# CMC.net
KiCad netlist of a schematic drawn in Altium Designer
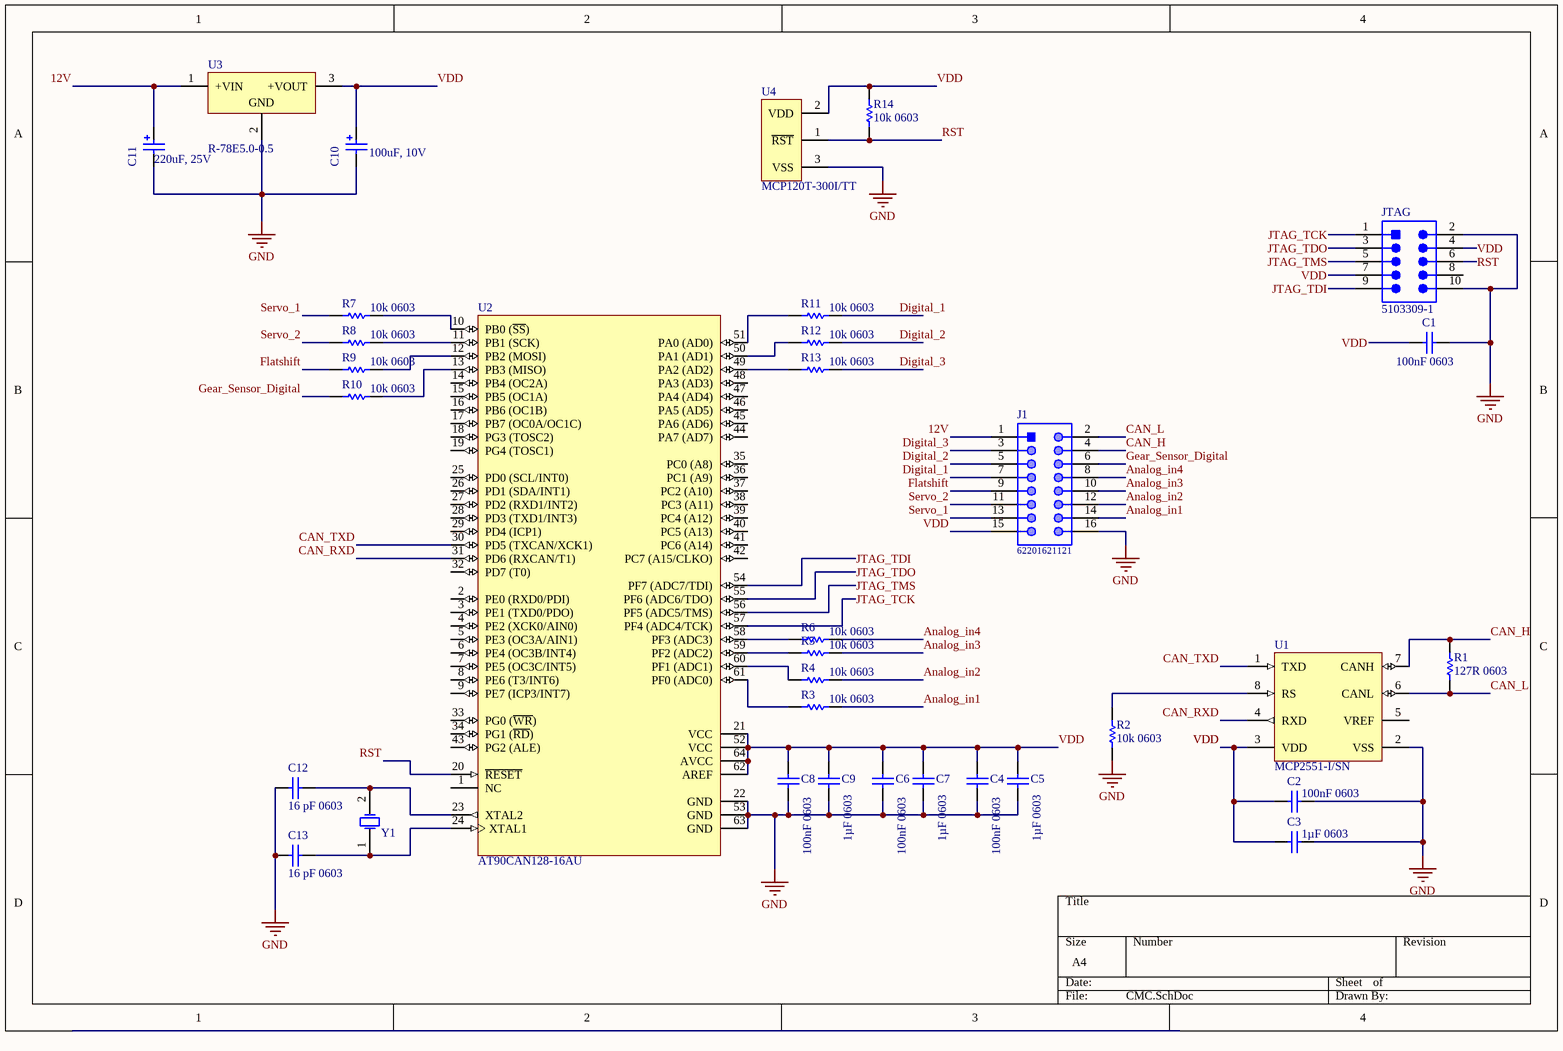
[diagram p0: CMC.SchDoc]

(export (version "E")
  (design (tool "Eeschema 10.0.6"))
  (components
    (comp (ref "C1")
      (value "100nF 0603")
      (footprint "CAPC0603(1608)100_L")
      (description "CAP 100nF 10V ±5% 0603 (1608 Metric) Thickness 1mm SMD")
      (fields (field (name "TOLERANCE") "Â±5%"))
      (libsource (lib "Altium Content Vault") (part "CAP"))
    )
    (comp (ref "C2")
      (value "100nF 0603")
      (footprint "CAPC0603(1608)100_L")
      (description "CAP 100nF 10V ±5% 0603 (1608 Metric) Thickness 1mm SMD")
      (fields (field (name "TOLERANCE") "Â±5%"))
      (libsource (lib "Altium Content Vault") (part "CAP"))
    )
    (comp (ref "C3")
      (value "1µF 0603")
      (footprint "CAPC0603(1608)100_L")
      (description "CAP 100nF 10V ±5% 0603 (1608 Metric) Thickness 1mm SMD")
      (fields (field (name "TOLERANCE") "Â±5%"))
      (libsource (lib "Altium Content Vault") (part "CAP"))
    )
    (comp (ref "C4")
      (value "100nF 0603")
      (footprint "CAPC0603(1608)100_L")
      (description "CAP 100nF 10V ±5% 0603 (1608 Metric) Thickness 1mm SMD")
      (fields (field (name "TOLERANCE") "Â±5%"))
      (libsource (lib "Altium Content Vault") (part "CAP"))
    )
    (comp (ref "C5")
      (value "1µF 0603")
      (footprint "CAPC0603(1608)100_L")
      (description "CAP 100nF 10V ±5% 0603 (1608 Metric) Thickness 1mm SMD")
      (fields (field (name "TOLERANCE") "Â±5%"))
      (libsource (lib "Altium Content Vault") (part "CAP"))
    )
    (comp (ref "C6")
      (value "100nF 0603")
      (footprint "CAPC0603(1608)100_L")
      (description "CAP 100nF 10V ±5% 0603 (1608 Metric) Thickness 1mm SMD")
      (fields (field (name "TOLERANCE") "Â±5%"))
      (libsource (lib "Altium Content Vault") (part "CAP"))
    )
    (comp (ref "C7")
      (value "1µF 0603")
      (footprint "CAPC0603(1608)100_L")
      (description "CAP 100nF 10V ±5% 0603 (1608 Metric) Thickness 1mm SMD")
      (fields (field (name "TOLERANCE") "Â±5%"))
      (libsource (lib "Altium Content Vault") (part "CAP"))
    )
    (comp (ref "C8")
      (value "100nF 0603")
      (footprint "CAPC0603(1608)100_L")
      (description "CAP 100nF 10V ±5% 0603 (1608 Metric) Thickness 1mm SMD")
      (fields (field (name "TOLERANCE") "Â±5%"))
      (libsource (lib "Altium Content Vault") (part "CAP"))
    )
    (comp (ref "C9")
      (value "1µF 0603")
      (footprint "CAPC0603(1608)100_L")
      (description "CAP 100nF 10V ±5% 0603 (1608 Metric) Thickness 1mm SMD")
      (fields (field (name "TOLERANCE") "Â±5%"))
      (libsource (lib "Altium Content Vault") (part "CAP"))
    )
    (comp (ref "C10")
      (value "100uF, 10V")
      (footprint "WCAP-ASLU_6.3x7.7")
      (description "WCAP-ASLU Aluminium Electrolytic Capacitors, D6.3mm x L7.7mm, 100uF, +/-20%, 10VDC")
      (fields (field (name "PART NUMBER") "865090245005") (field (name "PUBLISHER") "Wurth Elektronik"))
      (libsource (lib "Altium_WCAP-ASLU (rev19a)") (part "865090245005"))
    )
    (comp (ref "C11")
      (value "220uF, 25V")
      (footprint "WCAP-ATET_10x12.5")
      (description "WCAP-ATET THT Aluminum Electrolytic Capacitors, D10mm x L12.5mm, 220uF, +/-20%, 25VDC")
      (fields (field (name "PART NUMBER") "860130475006") (field (name "PUBLISHER") "Wurth Elektronik"))
      (libsource (lib "Altium_WCAP-ATET (rev19a)") (part "860130475006"))
    )
    (comp (ref "C12")
      (value "16 pF 0603")
      (footprint "CAPC0603(1608)100_L")
      (description "CAP 100nF 10V ±5% 0603 (1608 Metric) Thickness 1mm SMD")
      (fields (field (name "TOLERANCE") "Â±5%"))
      (libsource (lib "Altium Content Vault") (part "CAP"))
    )
    (comp (ref "C13")
      (value "16 pF 0603")
      (footprint "CAPC0603(1608)100_L")
      (description "CAP 100nF 10V ±5% 0603 (1608 Metric) Thickness 1mm SMD")
      (fields (field (name "TOLERANCE") "Â±5%"))
      (libsource (lib "Altium Content Vault") (part "CAP"))
    )
    (comp (ref "J1")
      (value "62201621121")
      (footprint "62201621121")
      (description "THT Vertical Pin Header WR-PHD, Pitch 1.27 mm, Dual Row, 16 pins")
      (fields (field (name "MANUFACTURER") "Wurth Elektronik") (field (name "PUBLISHER") "WurthElektronik"))
      (libsource (lib "Altium Content Vault") (part "WE-CN-2P-M-R16"))
    )
    (comp (ref "JTAG")
      (value "5103309-1")
      (footprint "TECO-5103309-1_V")
      (fields (field (name "MANUFACTURER") "TE Connectivity"))
      (libsource (lib "Altium Content Vault") (part "CN-2P-M-R10"))
    )
    (comp (ref "R1")
      (value "127R 0603")
      (footprint "RESC0603(1608)_N")
      (description "127R 0.1W 1% 0603 (1608 Metric)  SMD")
      (fields (field (name "POWER") "0.1 W") (field (name "TOLERANCE") "1 %"))
      (libsource (lib "Altium Content Vault") (part "RES"))
    )
    (comp (ref "R2")
      (value "10k 0603")
      (footprint "RESC0603(1608)_N")
      (description "127R 0.1W 1% 0603 (1608 Metric)  SMD")
      (fields (field (name "POWER") "0.1 W") (field (name "TOLERANCE") "1 %"))
      (libsource (lib "Altium Content Vault") (part "RES"))
    )
    (comp (ref "R3")
      (value "10k 0603")
      (footprint "RESC0603(1608)_N")
      (description "127R 0.1W 1% 0603 (1608 Metric)  SMD")
      (fields (field (name "POWER") "0.1 W") (field (name "TOLERANCE") "1 %"))
      (libsource (lib "Altium Content Vault") (part "RES"))
    )
    (comp (ref "R4")
      (value "10k 0603")
      (footprint "RESC0603(1608)_N")
      (description "127R 0.1W 1% 0603 (1608 Metric)  SMD")
      (fields (field (name "POWER") "0.1 W") (field (name "TOLERANCE") "1 %"))
      (libsource (lib "Altium Content Vault") (part "RES"))
    )
    (comp (ref "R5")
      (value "10k 0603")
      (footprint "RESC0603(1608)_N")
      (description "127R 0.1W 1% 0603 (1608 Metric)  SMD")
      (fields (field (name "POWER") "0.1 W") (field (name "TOLERANCE") "1 %"))
      (libsource (lib "Altium Content Vault") (part "RES"))
    )
    (comp (ref "R6")
      (value "10k 0603")
      (footprint "RESC0603(1608)_N")
      (description "127R 0.1W 1% 0603 (1608 Metric)  SMD")
      (fields (field (name "POWER") "0.1 W") (field (name "TOLERANCE") "1 %"))
      (libsource (lib "Altium Content Vault") (part "RES"))
    )
    (comp (ref "R7")
      (value "10k 0603")
      (footprint "RESC0603(1608)_N")
      (description "127R 0.1W 1% 0603 (1608 Metric)  SMD")
      (fields (field (name "POWER") "0.1 W") (field (name "TOLERANCE") "1 %"))
      (libsource (lib "Altium Content Vault") (part "RES"))
    )
    (comp (ref "R8")
      (value "10k 0603")
      (footprint "RESC0603(1608)_N")
      (description "127R 0.1W 1% 0603 (1608 Metric)  SMD")
      (fields (field (name "POWER") "0.1 W") (field (name "TOLERANCE") "1 %"))
      (libsource (lib "Altium Content Vault") (part "RES"))
    )
    (comp (ref "R9")
      (value "10k 0603")
      (footprint "RESC0603(1608)_N")
      (description "127R 0.1W 1% 0603 (1608 Metric)  SMD")
      (fields (field (name "POWER") "0.1 W") (field (name "TOLERANCE") "1 %"))
      (libsource (lib "Altium Content Vault") (part "RES"))
    )
    (comp (ref "R10")
      (value "10k 0603")
      (footprint "RESC0603(1608)_N")
      (description "127R 0.1W 1% 0603 (1608 Metric)  SMD")
      (fields (field (name "POWER") "0.1 W") (field (name "TOLERANCE") "1 %"))
      (libsource (lib "Altium Content Vault") (part "RES"))
    )
    (comp (ref "R11")
      (value "10k 0603")
      (footprint "RESC0603(1608)_N")
      (description "127R 0.1W 1% 0603 (1608 Metric)  SMD")
      (fields (field (name "POWER") "0.1 W") (field (name "TOLERANCE") "1 %"))
      (libsource (lib "Altium Content Vault") (part "RES"))
    )
    (comp (ref "R12")
      (value "10k 0603")
      (footprint "RESC0603(1608)_N")
      (description "127R 0.1W 1% 0603 (1608 Metric)  SMD")
      (fields (field (name "POWER") "0.1 W") (field (name "TOLERANCE") "1 %"))
      (libsource (lib "Altium Content Vault") (part "RES"))
    )
    (comp (ref "R13")
      (value "10k 0603")
      (footprint "RESC0603(1608)_N")
      (description "127R 0.1W 1% 0603 (1608 Metric)  SMD")
      (fields (field (name "POWER") "0.1 W") (field (name "TOLERANCE") "1 %"))
      (libsource (lib "Altium Content Vault") (part "RES"))
    )
    (comp (ref "R14")
      (value "10k 0603")
      (footprint "RESC0603(1608)_N")
      (description "127R 0.1W 1% 0603 (1608 Metric)  SMD")
      (fields (field (name "POWER") "0.1 W") (field (name "TOLERANCE") "1 %"))
      (libsource (lib "Altium Content Vault") (part "RES"))
    )
    (comp (ref "U1")
      (value "MCP2551-I/SN")
      (footprint "MCHP-SN8_V")
      (fields (field (name "MANUFACTURER") "Microchip"))
      (libsource (lib "Altium Content Vault") (part "MCHP-MCP2551-SN8"))
    )
    (comp (ref "U2")
      (value "AT90CAN128-16AU")
      (footprint "64A_M")
      (libsource (lib "Altium Content Vault") (part "MC-8B-AT90CAN32-SQ64"))
    )
    (comp (ref "U3")
      (value "R-78E5.0-0.5")
      (footprint "REPO-R-78E-0.5-3_V")
      (description "DC/DC-Converter, 5 V Single Output, 500 mA, -40 to 85 degC, 3-Pin THD, RoHS, Tube")
      (fields (field (name "MANUFACTURER") "Recom Power"))
      (libsource (lib "Altium Content Vault") (part "REPO-R-78XX-3"))
    )
    (comp (ref "U4")
      (value "MCP120T-300I/TT")
      (footprint "SOT-23-TT3_N")
      (libsource (lib "Altium Content Vault") (part "PM-SCCT-MCP120-3"))
    )
    (comp (ref "Y1")
      (value "16MHz, +/-30ppm, 16pF")
      (footprint "WE-XTAL_HC49/4HSMX")
      (description "WE-XTAL Quartz Crystal, size HC49-4HSMX, 16MHz, +/-30ppm, 16pF")
      (fields (field (name "PART NUMBER") "830003237") (field (name "PUBLISHER") "Wurth Elektronik"))
      (libsource (lib "Altium_WE-XTAL (rev19a)") (part "830003237"))
    )
  )
  (nets
    (net (code "1") (name "/12V") (class "Default")
      (node (ref "C11") (pin "2") (pinfunction "P_2") (pintype "passive"))
      (node (ref "J1") (pin "1") (pinfunction "1_1") (pintype "passive"))
      (node (ref "U3") (pin "1") (pinfunction "+VIN_1") (pintype "power_in"))
    )
    (net (code "2") (name "/Analog_in1") (class "Default")
      (node (ref "J1") (pin "14") (pinfunction "14_14") (pintype "passive"))
      (node (ref "R3") (pin "1") (pinfunction "1_1") (pintype "passive"))
    )
    (net (code "3") (name "/Analog_in2") (class "Default")
      (node (ref "J1") (pin "12") (pinfunction "12_12") (pintype "passive"))
      (node (ref "R4") (pin "1") (pinfunction "1_1") (pintype "passive"))
    )
    (net (code "4") (name "/Analog_in3") (class "Default")
      (node (ref "J1") (pin "10") (pinfunction "10_10") (pintype "passive"))
      (node (ref "R5") (pin "1") (pinfunction "1_1") (pintype "passive"))
    )
    (net (code "5") (name "/Analog_in4") (class "Default")
      (node (ref "J1") (pin "8") (pinfunction "8_8") (pintype "passive"))
      (node (ref "R6") (pin "1") (pinfunction "1_1") (pintype "passive"))
    )
    (net (code "6") (name "/CAN_H") (class "Default")
      (node (ref "J1") (pin "4") (pinfunction "4_4") (pintype "passive"))
      (node (ref "R1") (pin "2") (pinfunction "2_2") (pintype "passive"))
      (node (ref "U1") (pin "7") (pinfunction "CANH_7") (pintype "bidirectional"))
    )
    (net (code "7") (name "/CAN_L") (class "Default")
      (node (ref "J1") (pin "2") (pinfunction "2_2") (pintype "passive"))
      (node (ref "R1") (pin "1") (pinfunction "1_1") (pintype "passive"))
      (node (ref "U1") (pin "6") (pinfunction "CANL_6") (pintype "bidirectional"))
    )
    (net (code "8") (name "/CAN_RXD") (class "Default")
      (node (ref "U1") (pin "4") (pinfunction "RXD_4") (pintype "output"))
      (node (ref "U2") (pin "31") (pinfunction "PD6_(RXCAN/T1)_31") (pintype "bidirectional"))
    )
    (net (code "9") (name "/CAN_TXD") (class "Default")
      (node (ref "U1") (pin "1") (pinfunction "TXD_1") (pintype "input"))
      (node (ref "U2") (pin "30") (pinfunction "PD5_(TXCAN/XCK1)_30") (pintype "bidirectional"))
    )
    (net (code "10") (name "/Digital_1") (class "Default")
      (node (ref "J1") (pin "7") (pinfunction "7_7") (pintype "passive"))
      (node (ref "R11") (pin "1") (pinfunction "1_1") (pintype "passive"))
    )
    (net (code "11") (name "/Digital_2") (class "Default")
      (node (ref "J1") (pin "5") (pinfunction "5_5") (pintype "passive"))
      (node (ref "R12") (pin "1") (pinfunction "1_1") (pintype "passive"))
    )
    (net (code "12") (name "/Digital_3") (class "Default")
      (node (ref "J1") (pin "3") (pinfunction "3_3") (pintype "passive"))
      (node (ref "R13") (pin "1") (pinfunction "1_1") (pintype "passive"))
    )
    (net (code "13") (name "/Flatshift") (class "Default")
      (node (ref "J1") (pin "9") (pinfunction "9_9") (pintype "passive"))
      (node (ref "R9") (pin "2") (pinfunction "2_2") (pintype "passive"))
    )
    (net (code "14") (name "/Gear_Sensor_Digital") (class "Default")
      (node (ref "J1") (pin "6") (pinfunction "6_6") (pintype "passive"))
      (node (ref "R10") (pin "2") (pinfunction "2_2") (pintype "passive"))
    )
    (net (code "15") (name "/JTAG_TCK") (class "Default")
      (node (ref "JTAG") (pin "1") (pinfunction "1_1") (pintype "passive"))
      (node (ref "U2") (pin "57") (pinfunction "PF4_(ADC4/TCK)_57") (pintype "bidirectional"))
    )
    (net (code "16") (name "/JTAG_TDI") (class "Default")
      (node (ref "JTAG") (pin "9") (pinfunction "9_9") (pintype "passive"))
      (node (ref "U2") (pin "54") (pinfunction "PF7_(ADC7/TDI)_54") (pintype "bidirectional"))
    )
    (net (code "17") (name "/JTAG_TDO") (class "Default")
      (node (ref "JTAG") (pin "3") (pinfunction "3_3") (pintype "passive"))
      (node (ref "U2") (pin "55") (pinfunction "PF6_(ADC6/TDO)_55") (pintype "bidirectional"))
    )
    (net (code "18") (name "/JTAG_TMS") (class "Default")
      (node (ref "JTAG") (pin "5") (pinfunction "5_5") (pintype "passive"))
      (node (ref "U2") (pin "56") (pinfunction "PF5_(ADC5/TMS)_56") (pintype "bidirectional"))
    )
    (net (code "19") (name "/RST") (class "Default")
      (node (ref "JTAG") (pin "6") (pinfunction "6_6") (pintype "passive"))
      (node (ref "R14") (pin "2") (pinfunction "2_2") (pintype "passive"))
      (node (ref "U2") (pin "20") (pinfunction "~{RESET}_20") (pintype "input"))
      (node (ref "U4") (pin "1") (pinfunction "~{RST}_1") (pintype "open_collector"))
    )
    (net (code "20") (name "/Servo_1") (class "Default")
      (node (ref "J1") (pin "13") (pinfunction "13_13") (pintype "passive"))
      (node (ref "R7") (pin "2") (pinfunction "2_2") (pintype "passive"))
    )
    (net (code "21") (name "/Servo_2") (class "Default")
      (node (ref "J1") (pin "11") (pinfunction "11_11") (pintype "passive"))
      (node (ref "R8") (pin "2") (pinfunction "2_2") (pintype "passive"))
    )
    (net (code "22") (name "/VDD") (class "Default")
      (node (ref "C1") (pin "1") (pinfunction "1_1") (pintype "passive"))
      (node (ref "C10") (pin "2") (pinfunction "P_2") (pintype "passive"))
      (node (ref "C2") (pin "1") (pinfunction "1_1") (pintype "passive"))
      (node (ref "C3") (pin "1") (pinfunction "1_1") (pintype "passive"))
      (node (ref "C4") (pin "2") (pinfunction "2_2") (pintype "passive"))
      (node (ref "C5") (pin "2") (pinfunction "2_2") (pintype "passive"))
      (node (ref "C6") (pin "2") (pinfunction "2_2") (pintype "passive"))
      (node (ref "C7") (pin "2") (pinfunction "2_2") (pintype "passive"))
      (node (ref "C8") (pin "2") (pinfunction "2_2") (pintype "passive"))
      (node (ref "C9") (pin "2") (pinfunction "2_2") (pintype "passive"))
      (node (ref "J1") (pin "15") (pinfunction "15_15") (pintype "passive"))
      (node (ref "JTAG") (pin "4") (pinfunction "4_4") (pintype "passive"))
      (node (ref "JTAG") (pin "7") (pinfunction "7_7") (pintype "passive"))
      (node (ref "R14") (pin "1") (pinfunction "1_1") (pintype "passive"))
      (node (ref "U1") (pin "3") (pinfunction "VDD_3") (pintype "power_in"))
      (node (ref "U2") (pin "21") (pinfunction "VCC_21") (pintype "power_in"))
      (node (ref "U2") (pin "52") (pinfunction "VCC_52") (pintype "power_in"))
      (node (ref "U2") (pin "62") (pinfunction "AREF_62") (pintype "power_in"))
      (node (ref "U2") (pin "64") (pinfunction "AVCC_64") (pintype "power_in"))
      (node (ref "U3") (pin "3") (pinfunction "+VOUT_3") (pintype "power_in"))
      (node (ref "U4") (pin "2") (pinfunction "VDD_2") (pintype "power_in"))
    )
    (net (code "23") (name "GND") (class "Default")
      (node (ref "C1") (pin "2") (pinfunction "2_2") (pintype "passive"))
      (node (ref "C10") (pin "1") (pinfunction "N_1") (pintype "passive"))
      (node (ref "C11") (pin "1") (pinfunction "N_1") (pintype "passive"))
      (node (ref "C12") (pin "2") (pinfunction "2_2") (pintype "passive"))
      (node (ref "C13") (pin "2") (pinfunction "2_2") (pintype "passive"))
      (node (ref "C2") (pin "2") (pinfunction "2_2") (pintype "passive"))
      (node (ref "C3") (pin "2") (pinfunction "2_2") (pintype "passive"))
      (node (ref "C4") (pin "1") (pinfunction "1_1") (pintype "passive"))
      (node (ref "C5") (pin "1") (pinfunction "1_1") (pintype "passive"))
      (node (ref "C6") (pin "1") (pinfunction "1_1") (pintype "passive"))
      (node (ref "C7") (pin "1") (pinfunction "1_1") (pintype "passive"))
      (node (ref "C8") (pin "1") (pinfunction "1_1") (pintype "passive"))
      (node (ref "C9") (pin "1") (pinfunction "1_1") (pintype "passive"))
      (node (ref "J1") (pin "16") (pinfunction "16_16") (pintype "passive"))
      (node (ref "JTAG") (pin "10") (pinfunction "10_10") (pintype "passive"))
      (node (ref "JTAG") (pin "2") (pinfunction "2_2") (pintype "passive"))
      (node (ref "R2") (pin "1") (pinfunction "1_1") (pintype "passive"))
      (node (ref "U1") (pin "2") (pinfunction "VSS_2") (pintype "power_in"))
      (node (ref "U2") (pin "22") (pinfunction "GND_22") (pintype "power_in"))
      (node (ref "U2") (pin "53") (pinfunction "GND_53") (pintype "power_in"))
      (node (ref "U2") (pin "63") (pinfunction "GND_63") (pintype "power_in"))
      (node (ref "U3") (pin "2") (pinfunction "GND_2") (pintype "power_in"))
      (node (ref "U4") (pin "3") (pinfunction "VSS_3") (pintype "power_in"))
    )
    (net (code "24") (name "Net-(U1-RS)") (class "Default")
      (node (ref "R2") (pin "2") (pinfunction "2_2") (pintype "passive"))
      (node (ref "U1") (pin "8") (pinfunction "RS_8") (pintype "input"))
    )
    (net (code "25") (name "Net-(U2-PA0_(AD0))") (class "Default")
      (node (ref "R11") (pin "2") (pinfunction "2_2") (pintype "passive"))
      (node (ref "U2") (pin "51") (pinfunction "PA0_(AD0)_51") (pintype "bidirectional"))
    )
    (net (code "26") (name "Net-(U2-PA1_(AD1))") (class "Default")
      (node (ref "R12") (pin "2") (pinfunction "2_2") (pintype "passive"))
      (node (ref "U2") (pin "50") (pinfunction "PA1_(AD1)_50") (pintype "bidirectional"))
    )
    (net (code "27") (name "Net-(U2-PA2_(AD2))") (class "Default")
      (node (ref "R13") (pin "2") (pinfunction "2_2") (pintype "passive"))
      (node (ref "U2") (pin "49") (pinfunction "PA2_(AD2)_49") (pintype "bidirectional"))
    )
    (net (code "28") (name "Net-(U2-PB0_(~{SS}))") (class "Default")
      (node (ref "R7") (pin "1") (pinfunction "1_1") (pintype "passive"))
      (node (ref "U2") (pin "10") (pinfunction "PB0_(~{SS})_10") (pintype "bidirectional"))
    )
    (net (code "29") (name "Net-(U2-PB1_(SCK))") (class "Default")
      (node (ref "R8") (pin "1") (pinfunction "1_1") (pintype "passive"))
      (node (ref "U2") (pin "11") (pinfunction "PB1_(SCK)_11") (pintype "bidirectional"))
    )
    (net (code "30") (name "Net-(U2-PB2_(MOSI))") (class "Default")
      (node (ref "R9") (pin "1") (pinfunction "1_1") (pintype "passive"))
      (node (ref "U2") (pin "12") (pinfunction "PB2_(MOSI)_12") (pintype "bidirectional"))
    )
    (net (code "31") (name "Net-(U2-PB3_(MISO))") (class "Default")
      (node (ref "R10") (pin "1") (pinfunction "1_1") (pintype "passive"))
      (node (ref "U2") (pin "13") (pinfunction "PB3_(MISO)_13") (pintype "bidirectional"))
    )
    (net (code "32") (name "Net-(U2-PF0_(ADC0))") (class "Default")
      (node (ref "R3") (pin "2") (pinfunction "2_2") (pintype "passive"))
      (node (ref "U2") (pin "61") (pinfunction "PF0_(ADC0)_61") (pintype "bidirectional"))
    )
    (net (code "33") (name "Net-(U2-PF1_(ADC1))") (class "Default")
      (node (ref "R4") (pin "2") (pinfunction "2_2") (pintype "passive"))
      (node (ref "U2") (pin "60") (pinfunction "PF1_(ADC1)_60") (pintype "bidirectional"))
    )
    (net (code "34") (name "Net-(U2-PF2_(ADC2))") (class "Default")
      (node (ref "R5") (pin "2") (pinfunction "2_2") (pintype "passive"))
      (node (ref "U2") (pin "59") (pinfunction "PF2_(ADC2)_59") (pintype "bidirectional"))
    )
    (net (code "35") (name "Net-(U2-PF3_(ADC3))") (class "Default")
      (node (ref "R6") (pin "2") (pinfunction "2_2") (pintype "passive"))
      (node (ref "U2") (pin "58") (pinfunction "PF3_(ADC3)_58") (pintype "bidirectional"))
    )
    (net (code "36") (name "Net-(U2-XTAL1)") (class "Default")
      (node (ref "C13") (pin "1") (pinfunction "1_1") (pintype "passive"))
      (node (ref "U2") (pin "24") (pinfunction "XTAL1_24") (pintype "input"))
      (node (ref "Y1") (pin "1") (pinfunction "OSC1_1") (pintype "passive"))
    )
    (net (code "37") (name "Net-(U2-XTAL2)") (class "Default")
      (node (ref "C12") (pin "1") (pinfunction "1_1") (pintype "passive"))
      (node (ref "U2") (pin "23") (pinfunction "XTAL2_23") (pintype "output"))
      (node (ref "Y1") (pin "2") (pinfunction "OSC2_2") (pintype "passive"))
    )
    (net (code "38") (name "unconnected-(JTAG-Pad8)") (class "Default")
      (node (ref "JTAG") (pin "8") (pinfunction "8_8") (pintype "passive"))
    )
    (net (code "39") (name "unconnected-(U1-VREF-Pad5)") (class "Default")
      (node (ref "U1") (pin "5") (pinfunction "VREF_5") (pintype "power_in"))
    )
    (net (code "40") (name "unconnected-(U2-NC-Pad1)") (class "Default")
      (node (ref "U2") (pin "1") (pinfunction "NC_1") (pintype "passive"))
    )
    (net (code "41") (name "unconnected-(U2-PA3_(AD3)-Pad48)") (class "Default")
      (node (ref "U2") (pin "48") (pinfunction "PA3_(AD3)_48") (pintype "bidirectional"))
    )
    (net (code "42") (name "unconnected-(U2-PA4_(AD4)-Pad47)") (class "Default")
      (node (ref "U2") (pin "47") (pinfunction "PA4_(AD4)_47") (pintype "bidirectional"))
    )
    (net (code "43") (name "unconnected-(U2-PA5_(AD5)-Pad46)") (class "Default")
      (node (ref "U2") (pin "46") (pinfunction "PA5_(AD5)_46") (pintype "bidirectional"))
    )
    (net (code "44") (name "unconnected-(U2-PA6_(AD6)-Pad45)") (class "Default")
      (node (ref "U2") (pin "45") (pinfunction "PA6_(AD6)_45") (pintype "bidirectional"))
    )
    (net (code "45") (name "unconnected-(U2-PA7_(AD7)-Pad44)") (class "Default")
      (node (ref "U2") (pin "44") (pinfunction "PA7_(AD7)_44") (pintype "bidirectional"))
    )
    (net (code "46") (name "unconnected-(U2-PB4_(OC2A)-Pad14)") (class "Default")
      (node (ref "U2") (pin "14") (pinfunction "PB4_(OC2A)_14") (pintype "bidirectional"))
    )
    (net (code "47") (name "unconnected-(U2-PB5_(OC1A)-Pad15)") (class "Default")
      (node (ref "U2") (pin "15") (pinfunction "PB5_(OC1A)_15") (pintype "bidirectional"))
    )
    (net (code "48") (name "unconnected-(U2-PB6_(OC1B)-Pad16)") (class "Default")
      (node (ref "U2") (pin "16") (pinfunction "PB6_(OC1B)_16") (pintype "bidirectional"))
    )
    (net (code "49") (name "unconnected-(U2-PB7_(OC0A{slash}OC1C)-Pad17)") (class "Default")
      (node (ref "U2") (pin "17") (pinfunction "PB7_(OC0A/OC1C)_17") (pintype "bidirectional"))
    )
    (net (code "50") (name "unconnected-(U2-PC0_(A8)-Pad35)") (class "Default")
      (node (ref "U2") (pin "35") (pinfunction "PC0_(A8)_35") (pintype "bidirectional"))
    )
    (net (code "51") (name "unconnected-(U2-PC1_(A9)-Pad36)") (class "Default")
      (node (ref "U2") (pin "36") (pinfunction "PC1_(A9)_36") (pintype "bidirectional"))
    )
    (net (code "52") (name "unconnected-(U2-PC2_(A10)-Pad37)") (class "Default")
      (node (ref "U2") (pin "37") (pinfunction "PC2_(A10)_37") (pintype "bidirectional"))
    )
    (net (code "53") (name "unconnected-(U2-PC3_(A11)-Pad38)") (class "Default")
      (node (ref "U2") (pin "38") (pinfunction "PC3_(A11)_38") (pintype "bidirectional"))
    )
    (net (code "54") (name "unconnected-(U2-PC4_(A12)-Pad39)") (class "Default")
      (node (ref "U2") (pin "39") (pinfunction "PC4_(A12)_39") (pintype "bidirectional"))
    )
    (net (code "55") (name "unconnected-(U2-PC5_(A13)-Pad40)") (class "Default")
      (node (ref "U2") (pin "40") (pinfunction "PC5_(A13)_40") (pintype "bidirectional"))
    )
    (net (code "56") (name "unconnected-(U2-PC6_(A14)-Pad41)") (class "Default")
      (node (ref "U2") (pin "41") (pinfunction "PC6_(A14)_41") (pintype "bidirectional"))
    )
    (net (code "57") (name "unconnected-(U2-PC7_(A15{slash}CLKO)-Pad42)") (class "Default")
      (node (ref "U2") (pin "42") (pinfunction "PC7_(A15/CLKO)_42") (pintype "bidirectional"))
    )
    (net (code "58") (name "unconnected-(U2-PD0_(SCL{slash}INT0)-Pad25)") (class "Default")
      (node (ref "U2") (pin "25") (pinfunction "PD0_(SCL/INT0)_25") (pintype "bidirectional"))
    )
    (net (code "59") (name "unconnected-(U2-PD1_(SDA{slash}INT1)-Pad26)") (class "Default")
      (node (ref "U2") (pin "26") (pinfunction "PD1_(SDA/INT1)_26") (pintype "bidirectional"))
    )
    (net (code "60") (name "unconnected-(U2-PD2_(RXD1{slash}INT2)-Pad27)") (class "Default")
      (node (ref "U2") (pin "27") (pinfunction "PD2_(RXD1/INT2)_27") (pintype "bidirectional"))
    )
    (net (code "61") (name "unconnected-(U2-PD3_(TXD1{slash}INT3)-Pad28)") (class "Default")
      (node (ref "U2") (pin "28") (pinfunction "PD3_(TXD1/INT3)_28") (pintype "bidirectional"))
    )
    (net (code "62") (name "unconnected-(U2-PD4_(ICP1)-Pad29)") (class "Default")
      (node (ref "U2") (pin "29") (pinfunction "PD4_(ICP1)_29") (pintype "bidirectional"))
    )
    (net (code "63") (name "unconnected-(U2-PD7_(T0)-Pad32)") (class "Default")
      (node (ref "U2") (pin "32") (pinfunction "PD7_(T0)_32") (pintype "bidirectional"))
    )
    (net (code "64") (name "unconnected-(U2-PE0_(RXD0{slash}PDI)-Pad2)") (class "Default")
      (node (ref "U2") (pin "2") (pinfunction "PE0_(RXD0/PDI)_2") (pintype "bidirectional"))
    )
    (net (code "65") (name "unconnected-(U2-PE1_(TXD0{slash}PDO)-Pad3)") (class "Default")
      (node (ref "U2") (pin "3") (pinfunction "PE1_(TXD0/PDO)_3") (pintype "bidirectional"))
    )
    (net (code "66") (name "unconnected-(U2-PE2_(XCK0{slash}AIN0)-Pad4)") (class "Default")
      (node (ref "U2") (pin "4") (pinfunction "PE2_(XCK0/AIN0)_4") (pintype "bidirectional"))
    )
    (net (code "67") (name "unconnected-(U2-PE3_(OC3A{slash}AIN1)-Pad5)") (class "Default")
      (node (ref "U2") (pin "5") (pinfunction "PE3_(OC3A/AIN1)_5") (pintype "bidirectional"))
    )
    (net (code "68") (name "unconnected-(U2-PE4_(OC3B{slash}INT4)-Pad6)") (class "Default")
      (node (ref "U2") (pin "6") (pinfunction "PE4_(OC3B/INT4)_6") (pintype "bidirectional"))
    )
    (net (code "69") (name "unconnected-(U2-PE5_(OC3C{slash}INT5)-Pad7)") (class "Default")
      (node (ref "U2") (pin "7") (pinfunction "PE5_(OC3C/INT5)_7") (pintype "bidirectional"))
    )
    (net (code "70") (name "unconnected-(U2-PE6_(T3{slash}INT6)-Pad8)") (class "Default")
      (node (ref "U2") (pin "8") (pinfunction "PE6_(T3/INT6)_8") (pintype "bidirectional"))
    )
    (net (code "71") (name "unconnected-(U2-PE7_(ICP3{slash}INT7)-Pad9)") (class "Default")
      (node (ref "U2") (pin "9") (pinfunction "PE7_(ICP3/INT7)_9") (pintype "bidirectional"))
    )
    (net (code "72") (name "unconnected-(U2-PG0_(~{WR})-Pad33)") (class "Default")
      (node (ref "U2") (pin "33") (pinfunction "PG0_(~{WR})_33") (pintype "bidirectional"))
    )
    (net (code "73") (name "unconnected-(U2-PG1_(~{RD})-Pad34)") (class "Default")
      (node (ref "U2") (pin "34") (pinfunction "PG1_(~{RD})_34") (pintype "bidirectional"))
    )
    (net (code "74") (name "unconnected-(U2-PG2_(ALE)-Pad43)") (class "Default")
      (node (ref "U2") (pin "43") (pinfunction "PG2_(ALE)_43") (pintype "bidirectional"))
    )
    (net (code "75") (name "unconnected-(U2-PG3_(TOSC2)-Pad18)") (class "Default")
      (node (ref "U2") (pin "18") (pinfunction "PG3_(TOSC2)_18") (pintype "bidirectional"))
    )
    (net (code "76") (name "unconnected-(U2-PG4_(TOSC1)-Pad19)") (class "Default")
      (node (ref "U2") (pin "19") (pinfunction "PG4_(TOSC1)_19") (pintype "bidirectional"))
    )
  )
)
